# MRCS-Tiny-Servo-Pots.net
KiCad netlist of a schematic drawn in EAGLE
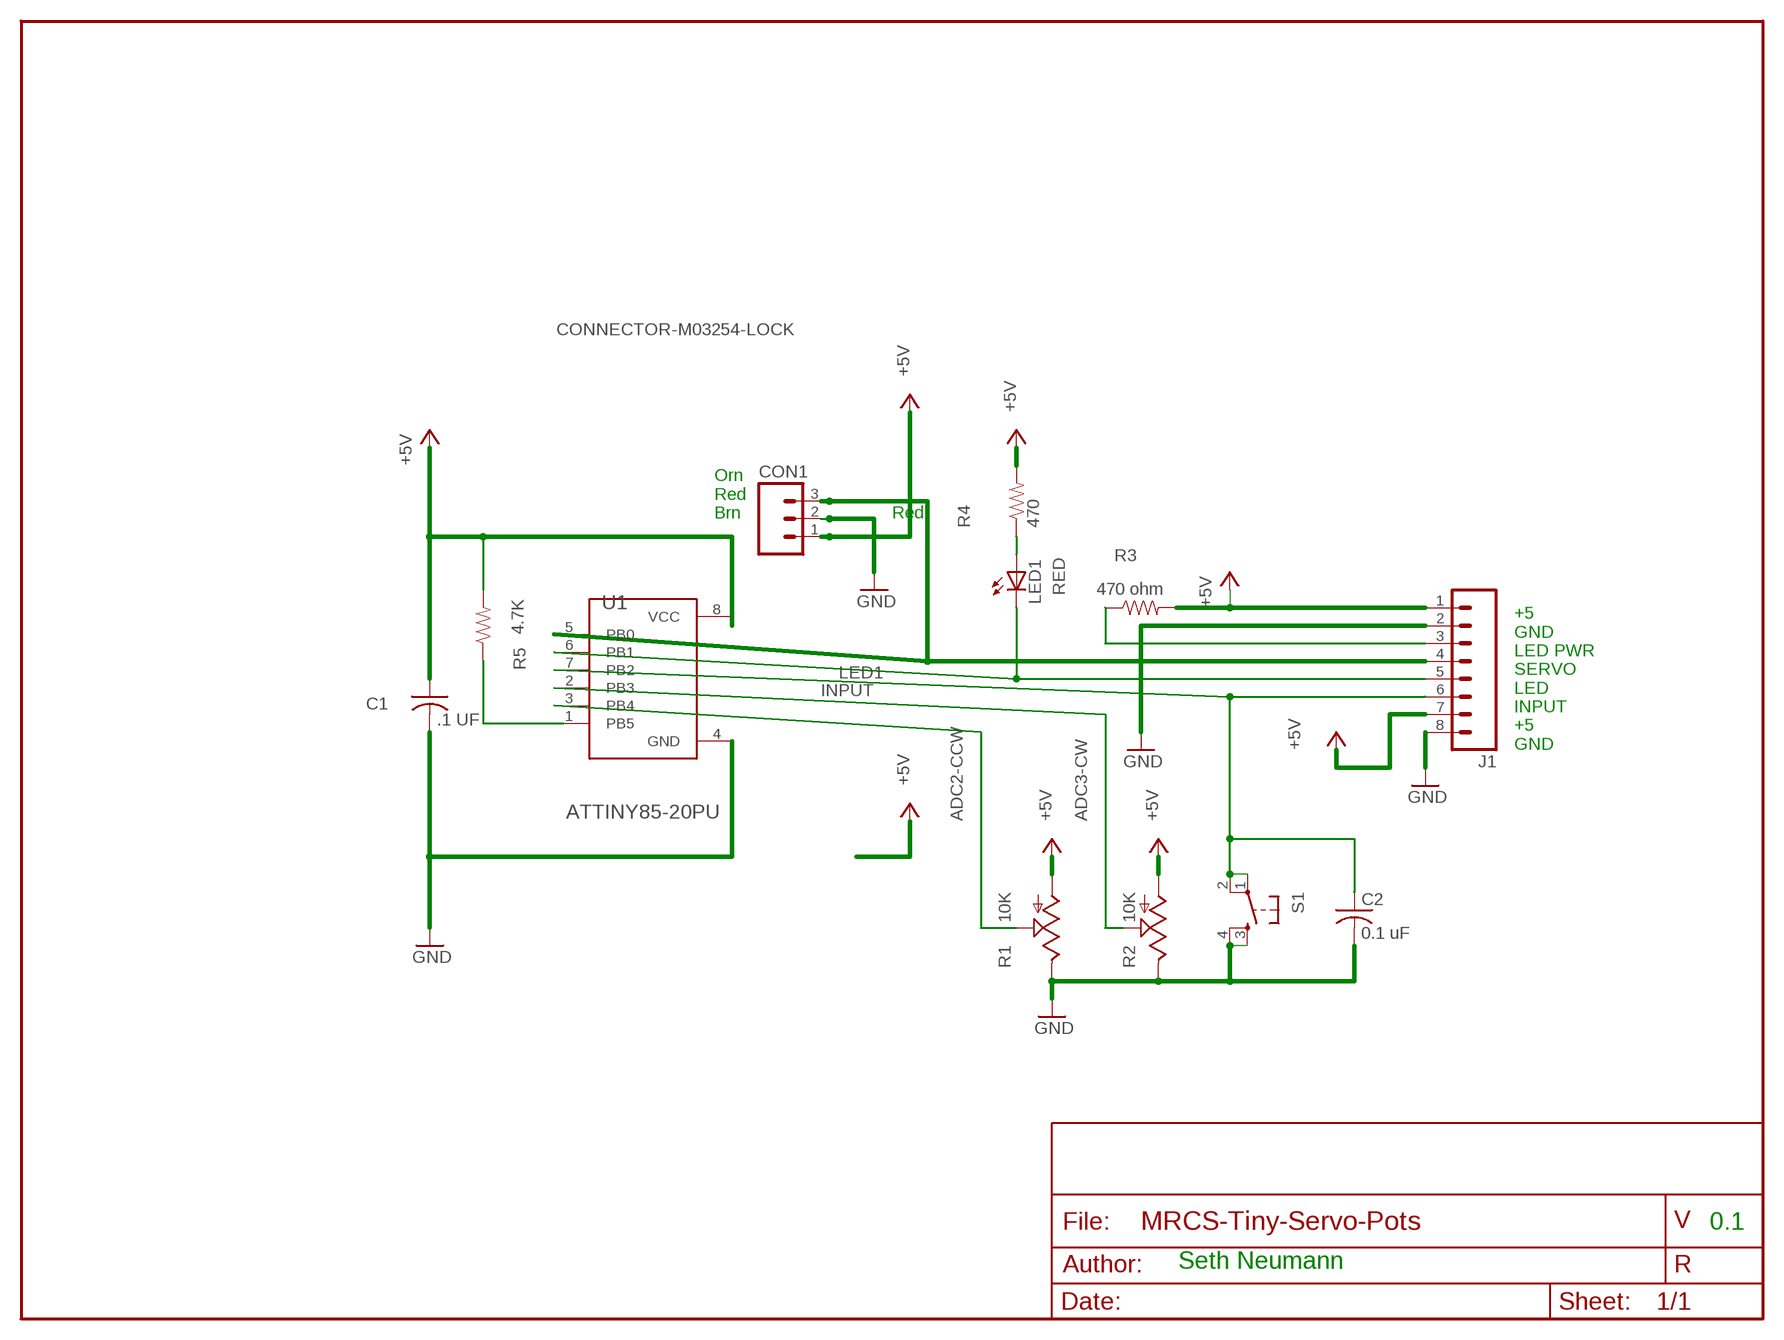
[diagram p0: schematic, sheet 1]

(export (version "E")
  (design (tool "Eeschema 10.0.6"))
  (components
    (comp (ref "C1")
      (value ".1 UF")
      (footprint "eagle-import:C-PTH-0.100")
      (libsource (lib "eagle-import") (part "CAPPTH2"))
    )
    (comp (ref "C2")
      (value "0.1 uF")
      (footprint "eagle-import:C-PTH-0.100")
      (libsource (lib "eagle-import") (part "CAPPTH2"))
    )
    (comp (ref "CON1")
      (value "CONNECTOR-M03254-LOCK")
      (footprint "eagle-import:3POL254")
      (libsource (lib "eagle-import") (part "CONNECTOR-M03254-LOCK"))
    )
    (comp (ref "J1")
      (value "CONNECTOR-M08LOCK")
      (footprint "eagle-import:1X08_LOCK")
      (libsource (lib "eagle-import") (part "CONNECTOR-M08LOCK"))
    )
    (comp (ref "LED1")
      (value "RED")
      (footprint "eagle-import:LED3MM")
      (libsource (lib "eagle-import") (part "LEDLED3MM"))
    )
    (comp (ref "R1")
      (value "10K")
      (footprint "eagle-import:RS3")
      (libsource (lib "eagle-import") (part "TRIM_US-RS3"))
    )
    (comp (ref "R2")
      (value "10K")
      (footprint "eagle-import:RS3")
      (libsource (lib "eagle-import") (part "TRIM_US-RS3"))
    )
    (comp (ref "R3")
      (value "470 ohm")
      (footprint "eagle-import:AXIAL-0.4-RES")
      (libsource (lib "eagle-import") (part "RPTH04"))
    )
    (comp (ref "R4")
      (value "470")
      (footprint "eagle-import:AXIAL-0.4-RES")
      (libsource (lib "eagle-import") (part "RPTH04"))
    )
    (comp (ref "R5")
      (value "4.7K")
      (footprint "eagle-import:AXIAL-0.4-RES")
      (libsource (lib "eagle-import") (part "RPTH04"))
    )
    (comp (ref "S1")
      (value "TAC_SWITCHPTH")
      (footprint "eagle-import:TACTILE-PTH")
      (libsource (lib "eagle-import") (part "TAC_SWITCHPTH"))
    )
    (comp (ref "U1")
      (value "ATTINY85-20PU")
      (footprint "eagle-import:DIP762W46P254L927H533Q8B")
      (fields (field (name "MF") "Microchip Technology / Atmel"))
      (libsource (lib "eagle-import") (part "ATTINY85-20PU"))
    )
  )
  (nets
    (net (code "1") (name "+5V") (class "Default")
      (node (ref "C1") (pin "1") (pinfunction "1_1") (pintype "passive"))
      (node (ref "CON1") (pin "1") (pinfunction "1_1") (pintype "passive"))
      (node (ref "J1") (pin "1") (pinfunction "1_1") (pintype "passive"))
      (node (ref "J1") (pin "7") (pinfunction "7_7") (pintype "passive"))
      (node (ref "R1") (pin "A") (pinfunction "A_A") (pintype "passive"))
      (node (ref "R2") (pin "A") (pinfunction "A_A") (pintype "passive"))
      (node (ref "R3") (pin "P$2") (pinfunction "2_P$2") (pintype "passive"))
      (node (ref "R4") (pin "P$2") (pinfunction "2_P$2") (pintype "passive"))
      (node (ref "R5") (pin "P$2") (pinfunction "2_P$2") (pintype "passive"))
    )
    (net (code "2") (name "/ADC2-CCW") (class "Default")
      (node (ref "R1") (pin "S") (pinfunction "S_S") (pintype "passive"))
      (node (ref "U1") (pin "3") (pinfunction "PB4_3") (pintype "bidirectional"))
    )
    (net (code "3") (name "/ADC3-CW") (class "Default")
      (node (ref "R2") (pin "S") (pinfunction "S_S") (pintype "passive"))
      (node (ref "U1") (pin "2") (pinfunction "PB3_2") (pintype "bidirectional"))
    )
    (net (code "4") (name "/INPUT") (class "Default")
      (node (ref "C2") (pin "1") (pinfunction "1_1") (pintype "passive"))
      (node (ref "J1") (pin "6") (pinfunction "6_6") (pintype "passive"))
      (node (ref "S1") (pin "1") (pinfunction "1_1") (pintype "passive"))
      (node (ref "S1") (pin "2") (pinfunction "2_2") (pintype "passive"))
      (node (ref "U1") (pin "7") (pinfunction "PB2_7") (pintype "bidirectional"))
    )
    (net (code "5") (name "/LED1") (class "Default")
      (node (ref "J1") (pin "5") (pinfunction "5_5") (pintype "passive"))
      (node (ref "LED1") (pin "K") (pinfunction "C_K") (pintype "passive"))
      (node (ref "U1") (pin "6") (pinfunction "PB1_6") (pintype "bidirectional"))
    )
    (net (code "6") (name "/VCC") (class "Default")
      (node (ref "U1") (pin "8") (pinfunction "VCC_8") (pintype "power_in"))
    )
    (net (code "7") (name "GND") (class "Default")
      (node (ref "C1") (pin "2") (pinfunction "2_2") (pintype "passive"))
      (node (ref "C2") (pin "2") (pinfunction "2_2") (pintype "passive"))
      (node (ref "CON1") (pin "2") (pinfunction "2_2") (pintype "passive"))
      (node (ref "J1") (pin "2") (pinfunction "2_2") (pintype "passive"))
      (node (ref "J1") (pin "8") (pinfunction "8_8") (pintype "passive"))
      (node (ref "R1") (pin "E") (pinfunction "E_E") (pintype "passive"))
      (node (ref "R2") (pin "E") (pinfunction "E_E") (pintype "passive"))
      (node (ref "S1") (pin "3") (pinfunction "3_3") (pintype "passive"))
      (node (ref "S1") (pin "4") (pinfunction "4_4") (pintype "passive"))
      (node (ref "U1") (pin "4") (pinfunction "GND_4") (pintype "power_in"))
    )
    (net (code "8") (name "Net-(R3-1)") (class "Default")
      (node (ref "J1") (pin "3") (pinfunction "3_3") (pintype "passive"))
      (node (ref "R3") (pin "P$1") (pinfunction "1_P$1") (pintype "passive"))
    )
    (net (code "9") (name "Net-(R4-1)") (class "Default")
      (node (ref "LED1") (pin "A") (pinfunction "A_A") (pintype "passive"))
      (node (ref "R4") (pin "P$1") (pinfunction "1_P$1") (pintype "passive"))
    )
    (net (code "10") (name "Net-(U1-PB0)") (class "Default")
      (node (ref "CON1") (pin "3") (pinfunction "3_3") (pintype "passive"))
      (node (ref "J1") (pin "4") (pinfunction "4_4") (pintype "passive"))
      (node (ref "U1") (pin "5") (pinfunction "PB0_5") (pintype "bidirectional"))
    )
    (net (code "11") (name "unconnected-(R5-1-PadP$1)") (class "Default")
      (node (ref "R5") (pin "P$1") (pinfunction "1_P$1") (pintype "passive"))
    )
    (net (code "12") (name "unconnected-(U1-PB5-Pad1)") (class "Default")
      (node (ref "U1") (pin "1") (pinfunction "PB5_1") (pintype "bidirectional"))
    )
  )
)
